# Shunt_Board_V1_0.net
KiCad netlist of a schematic drawn in EAGLE
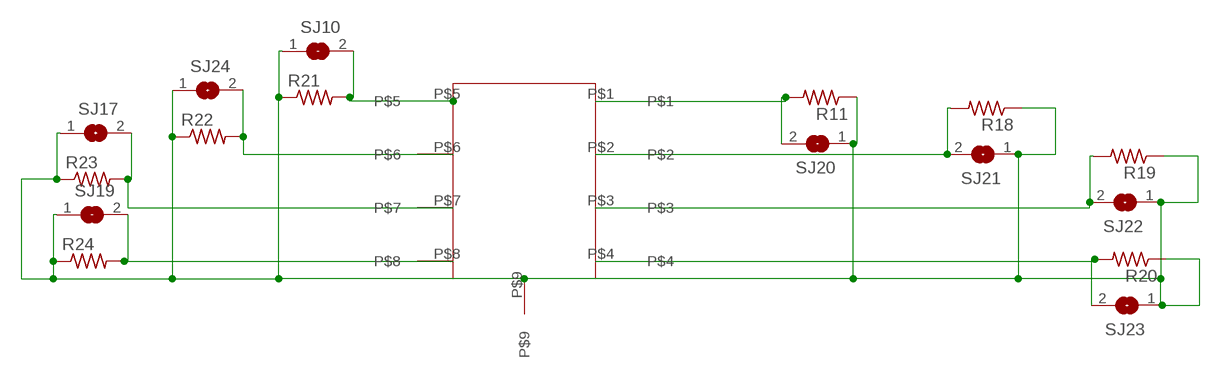
[diagram p0: schematic, sheet 1]

(export (version "E")
  (design (tool "Eeschema 10.0.6"))
  (components
    (comp (ref "R11")
      (value "R-US_0204/5")
      (footprint "eagle-import:0204_5")
      (libsource (lib "eagle-import") (part "R-US_0204/5"))
    )
    (comp (ref "R18")
      (value "R-US_0204/5")
      (footprint "eagle-import:0204_5")
      (libsource (lib "eagle-import") (part "R-US_0204/5"))
    )
    (comp (ref "R19")
      (value "R-US_0204/5")
      (footprint "eagle-import:0204_5")
      (libsource (lib "eagle-import") (part "R-US_0204/5"))
    )
    (comp (ref "R20")
      (value "R-US_0204/5")
      (footprint "eagle-import:0204_5")
      (libsource (lib "eagle-import") (part "R-US_0204/5"))
    )
    (comp (ref "R21")
      (value "R-US_0204/5")
      (footprint "eagle-import:0204_5")
      (libsource (lib "eagle-import") (part "R-US_0204/5"))
    )
    (comp (ref "R22")
      (value "R-US_0204/5")
      (footprint "eagle-import:0204_5")
      (libsource (lib "eagle-import") (part "R-US_0204/5"))
    )
    (comp (ref "R23")
      (value "R-US_0204/5")
      (footprint "eagle-import:0204_5")
      (libsource (lib "eagle-import") (part "R-US_0204/5"))
    )
    (comp (ref "R24")
      (value "R-US_0204/5")
      (footprint "eagle-import:0204_5")
      (libsource (lib "eagle-import") (part "R-US_0204/5"))
    )
    (comp (ref "SJ10")
      (value "SJ")
      (footprint "eagle-import:SJ")
      (libsource (lib "eagle-import") (part "SJ"))
    )
    (comp (ref "SJ17")
      (value "SJ")
      (footprint "eagle-import:SJ")
      (libsource (lib "eagle-import") (part "SJ"))
    )
    (comp (ref "SJ19")
      (value "SJ")
      (footprint "eagle-import:SJ")
      (libsource (lib "eagle-import") (part "SJ"))
    )
    (comp (ref "SJ20")
      (value "SJ")
      (footprint "eagle-import:SJ")
      (libsource (lib "eagle-import") (part "SJ"))
    )
    (comp (ref "SJ21")
      (value "SJ")
      (footprint "eagle-import:SJ")
      (libsource (lib "eagle-import") (part "SJ"))
    )
    (comp (ref "SJ22")
      (value "SJ")
      (footprint "eagle-import:SJ")
      (libsource (lib "eagle-import") (part "SJ"))
    )
    (comp (ref "SJ23")
      (value "SJ")
      (footprint "eagle-import:SJ")
      (libsource (lib "eagle-import") (part "SJ"))
    )
    (comp (ref "SJ24")
      (value "SJ")
      (footprint "eagle-import:SJ")
      (libsource (lib "eagle-import") (part "SJ"))
    )
    (comp (ref "U$1")
      (value "SHUNT")
      (footprint "eagle-import:SHUNT")
      (libsource (lib "eagle-import") (part "SHUNT"))
    )
  )
  (nets
    (net (code "1") (name "Net-(R11-Pad1)") (class "Default")
      (node (ref "R11") (pin "1") (pinfunction "1_1") (pintype "passive"))
      (node (ref "R18") (pin "1") (pinfunction "1_1") (pintype "passive"))
      (node (ref "R19") (pin "1") (pinfunction "1_1") (pintype "passive"))
      (node (ref "R20") (pin "1") (pinfunction "1_1") (pintype "passive"))
      (node (ref "R21") (pin "1") (pinfunction "1_1") (pintype "passive"))
      (node (ref "R22") (pin "1") (pinfunction "1_1") (pintype "passive"))
      (node (ref "R23") (pin "1") (pinfunction "1_1") (pintype "passive"))
      (node (ref "R24") (pin "1") (pinfunction "1_1") (pintype "passive"))
      (node (ref "SJ10") (pin "1") (pinfunction "1_1") (pintype "passive"))
      (node (ref "SJ17") (pin "1") (pinfunction "1_1") (pintype "passive"))
      (node (ref "SJ19") (pin "1") (pinfunction "1_1") (pintype "passive"))
      (node (ref "SJ20") (pin "1") (pinfunction "1_1") (pintype "passive"))
      (node (ref "SJ21") (pin "1") (pinfunction "1_1") (pintype "passive"))
      (node (ref "SJ22") (pin "1") (pinfunction "1_1") (pintype "passive"))
      (node (ref "SJ23") (pin "1") (pinfunction "1_1") (pintype "passive"))
      (node (ref "SJ24") (pin "1") (pinfunction "1_1") (pintype "passive"))
      (node (ref "U$1") (pin "P$9") (pinfunction "P$9_P$9") (pintype "bidirectional"))
    )
    (net (code "2") (name "Net-(R11-Pad2)") (class "Default")
      (node (ref "R11") (pin "2") (pinfunction "2_2") (pintype "passive"))
      (node (ref "SJ20") (pin "2") (pinfunction "2_2") (pintype "passive"))
      (node (ref "U$1") (pin "P$1") (pinfunction "P$1_P$1") (pintype "bidirectional"))
    )
    (net (code "3") (name "Net-(R18-Pad2)") (class "Default")
      (node (ref "R18") (pin "2") (pinfunction "2_2") (pintype "passive"))
      (node (ref "SJ21") (pin "2") (pinfunction "2_2") (pintype "passive"))
      (node (ref "U$1") (pin "P$2") (pinfunction "P$2_P$2") (pintype "bidirectional"))
    )
    (net (code "4") (name "Net-(R19-Pad2)") (class "Default")
      (node (ref "R19") (pin "2") (pinfunction "2_2") (pintype "passive"))
      (node (ref "SJ22") (pin "2") (pinfunction "2_2") (pintype "passive"))
      (node (ref "U$1") (pin "P$3") (pinfunction "P$3_P$3") (pintype "bidirectional"))
    )
    (net (code "5") (name "Net-(R20-Pad2)") (class "Default")
      (node (ref "R20") (pin "2") (pinfunction "2_2") (pintype "passive"))
      (node (ref "SJ23") (pin "2") (pinfunction "2_2") (pintype "passive"))
      (node (ref "U$1") (pin "P$4") (pinfunction "P$4_P$4") (pintype "bidirectional"))
    )
    (net (code "6") (name "Net-(R21-Pad2)") (class "Default")
      (node (ref "R21") (pin "2") (pinfunction "2_2") (pintype "passive"))
      (node (ref "SJ10") (pin "2") (pinfunction "2_2") (pintype "passive"))
      (node (ref "U$1") (pin "P$5") (pinfunction "P$5_P$5") (pintype "bidirectional"))
    )
    (net (code "7") (name "Net-(R22-Pad2)") (class "Default")
      (node (ref "R22") (pin "2") (pinfunction "2_2") (pintype "passive"))
      (node (ref "SJ24") (pin "2") (pinfunction "2_2") (pintype "passive"))
      (node (ref "U$1") (pin "P$6") (pinfunction "P$6_P$6") (pintype "bidirectional"))
    )
    (net (code "8") (name "Net-(R23-Pad2)") (class "Default")
      (node (ref "R23") (pin "2") (pinfunction "2_2") (pintype "passive"))
      (node (ref "SJ17") (pin "2") (pinfunction "2_2") (pintype "passive"))
      (node (ref "U$1") (pin "P$7") (pinfunction "P$7_P$7") (pintype "bidirectional"))
    )
    (net (code "9") (name "Net-(R24-Pad2)") (class "Default")
      (node (ref "R24") (pin "2") (pinfunction "2_2") (pintype "passive"))
      (node (ref "SJ19") (pin "2") (pinfunction "2_2") (pintype "passive"))
      (node (ref "U$1") (pin "P$8") (pinfunction "P$8_P$8") (pintype "bidirectional"))
    )
  )
)
